# retro.net
KiCad netlist of a schematic drawn in Altium Designer
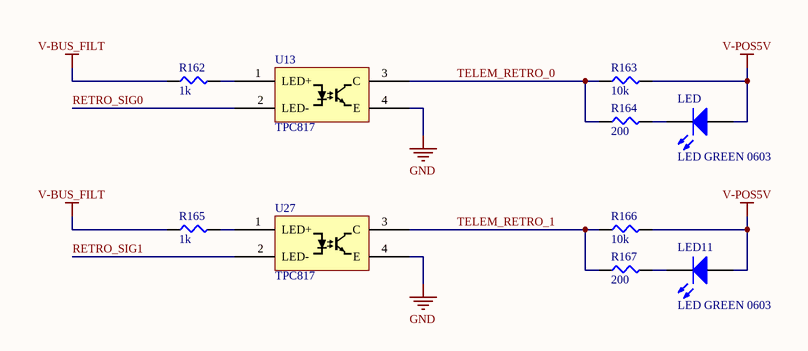
[diagram p0: retro.SchDoc]

(export (version "E")
  (design (tool "Eeschema 10.0.6"))
  (components
    (comp (ref "LED")
      (value "LED GREEN 0603")
      (footprint "LED 0603 GREEN")
      (fields (field (name "MANUFACTURER") "Lite-On Inc."))
      (libsource (lib "misc") (part "LED GREEN 0603"))
    )
    (comp (ref "LED11")
      (value "LED GREEN 0603")
      (footprint "LED 0603 GREEN")
      (fields (field (name "MANUFACTURER") "Lite-On Inc."))
      (libsource (lib "misc") (part "LED GREEN 0603"))
    )
    (comp (ref "R162")
      (value "1k")
      (footprint "SMD-0805-RES")
      (description "RES SMD 1K OHM 5% 1/2W 0805")
      (fields
        (field (name "PART NUMBER") "ERJ-P06J102V")
        (field (name "DIGI-KEY PART NUMBER") "P1.0KADCT-ND")
      )
      (libsource (lib "resistors") (part "ERJ-P06J102V"))
    )
    (comp (ref "R163")
      (value "10k")
      (footprint "SMD-0805-RES")
      (description "RES SMD 10K OHM 5% 1/2W 0805")
      (fields (field (name "PART NUMBER") "ERJ-P06J103V") (field (name "DIGI-KEY PART NUMBER") "P10KADCT-ND"))
      (libsource (lib "resistors") (part "ERJ-P06J103V"))
    )
    (comp (ref "R164")
      (value "200")
      (footprint "SMD-0805-RES")
      (description "RES SMD 200 OHM 1% 1/8W 0805")
      (fields (field (name "PART NUMBER") "ERJ-6ENF2000V") (field (name "DIGI-KEY PART NUMBER") "P200CCT-ND"))
      (libsource (lib "resistors") (part "ERJ-6ENF2000V"))
    )
    (comp (ref "R165")
      (value "1k")
      (footprint "SMD-0805-RES")
      (description "RES SMD 1K OHM 5% 1/2W 0805")
      (fields
        (field (name "PART NUMBER") "ERJ-P06J102V")
        (field (name "DIGI-KEY PART NUMBER") "P1.0KADCT-ND")
      )
      (libsource (lib "resistors") (part "ERJ-P06J102V"))
    )
    (comp (ref "R166")
      (value "10k")
      (footprint "SMD-0805-RES")
      (description "RES SMD 10K OHM 5% 1/2W 0805")
      (fields (field (name "PART NUMBER") "ERJ-P06J103V") (field (name "DIGI-KEY PART NUMBER") "P10KADCT-ND"))
      (libsource (lib "resistors") (part "ERJ-P06J103V"))
    )
    (comp (ref "R167")
      (value "200")
      (footprint "SMD-0805-RES")
      (description "RES SMD 200 OHM 1% 1/8W 0805")
      (fields (field (name "PART NUMBER") "ERJ-6ENF2000V") (field (name "DIGI-KEY PART NUMBER") "P200CCT-ND"))
      (libsource (lib "resistors") (part "ERJ-6ENF2000V"))
    )
    (comp (ref "U13")
      (value "TPC817")
      (footprint "SOT200P1005X328-5N")
      (description "OPTOISO 5KV TRANS 4SOP")
      (fields (field (name "MANUFACTURER") "Taiwan Semi"))
      (libsource (lib "ic") (part "TPC817"))
    )
    (comp (ref "U27")
      (value "TPC817")
      (footprint "SOT200P1005X328-5N")
      (description "OPTOISO 5KV TRANS 4SOP")
      (fields (field (name "MANUFACTURER") "Taiwan Semi"))
      (libsource (lib "ic") (part "TPC817"))
    )
  )
  (nets
    (net (code "1") (name "/RETRO_SIG0") (class "Default")
      (node (ref "U13") (pin "2") (pinfunction "LED-_2") (pintype "passive"))
    )
    (net (code "2") (name "/RETRO_SIG1") (class "Default")
      (node (ref "U27") (pin "2") (pinfunction "LED-_2") (pintype "passive"))
    )
    (net (code "3") (name "/TELEM_RETRO_0") (class "Default")
      (node (ref "R163") (pin "1") (pinfunction "1_1") (pintype "passive"))
      (node (ref "R164") (pin "1") (pinfunction "1_1") (pintype "passive"))
      (node (ref "U13") (pin "3") (pinfunction "C_3") (pintype "passive"))
    )
    (net (code "4") (name "/TELEM_RETRO_1") (class "Default")
      (node (ref "R166") (pin "1") (pinfunction "1_1") (pintype "passive"))
      (node (ref "R167") (pin "1") (pinfunction "1_1") (pintype "passive"))
      (node (ref "U27") (pin "3") (pinfunction "C_3") (pintype "passive"))
    )
    (net (code "5") (name "GND") (class "Default")
      (node (ref "U13") (pin "4") (pinfunction "E_4") (pintype "passive"))
      (node (ref "U27") (pin "4") (pinfunction "E_4") (pintype "passive"))
    )
    (net (code "6") (name "Net-(LED-K)") (class "Default")
      (node (ref "LED") (pin "2") (pinfunction "K_2") (pintype "passive"))
      (node (ref "R164") (pin "2") (pinfunction "2_2") (pintype "passive"))
    )
    (net (code "7") (name "Net-(LED11-K)") (class "Default")
      (node (ref "LED11") (pin "2") (pinfunction "K_2") (pintype "passive"))
      (node (ref "R167") (pin "2") (pinfunction "2_2") (pintype "passive"))
    )
    (net (code "8") (name "Net-(U13-LED+)") (class "Default")
      (node (ref "R162") (pin "2") (pinfunction "2_2") (pintype "passive"))
      (node (ref "U13") (pin "1") (pinfunction "LED+_1") (pintype "passive"))
    )
    (net (code "9") (name "Net-(U27-LED+)") (class "Default")
      (node (ref "R165") (pin "2") (pinfunction "2_2") (pintype "passive"))
      (node (ref "U27") (pin "1") (pinfunction "LED+_1") (pintype "passive"))
    )
    (net (code "10") (name "V-BUS_FILT") (class "Default")
      (node (ref "R162") (pin "1") (pinfunction "1_1") (pintype "passive"))
      (node (ref "R165") (pin "1") (pinfunction "1_1") (pintype "passive"))
    )
    (net (code "11") (name "V-POS5V") (class "Default")
      (node (ref "LED") (pin "1") (pinfunction "A_1") (pintype "passive"))
      (node (ref "LED11") (pin "1") (pinfunction "A_1") (pintype "passive"))
      (node (ref "R163") (pin "2") (pinfunction "2_2") (pintype "passive"))
      (node (ref "R166") (pin "2") (pinfunction "2_2") (pintype "passive"))
    )
  )
)
